# Teensy_Logger_Board.net
KiCad netlist of a schematic drawn in EAGLE
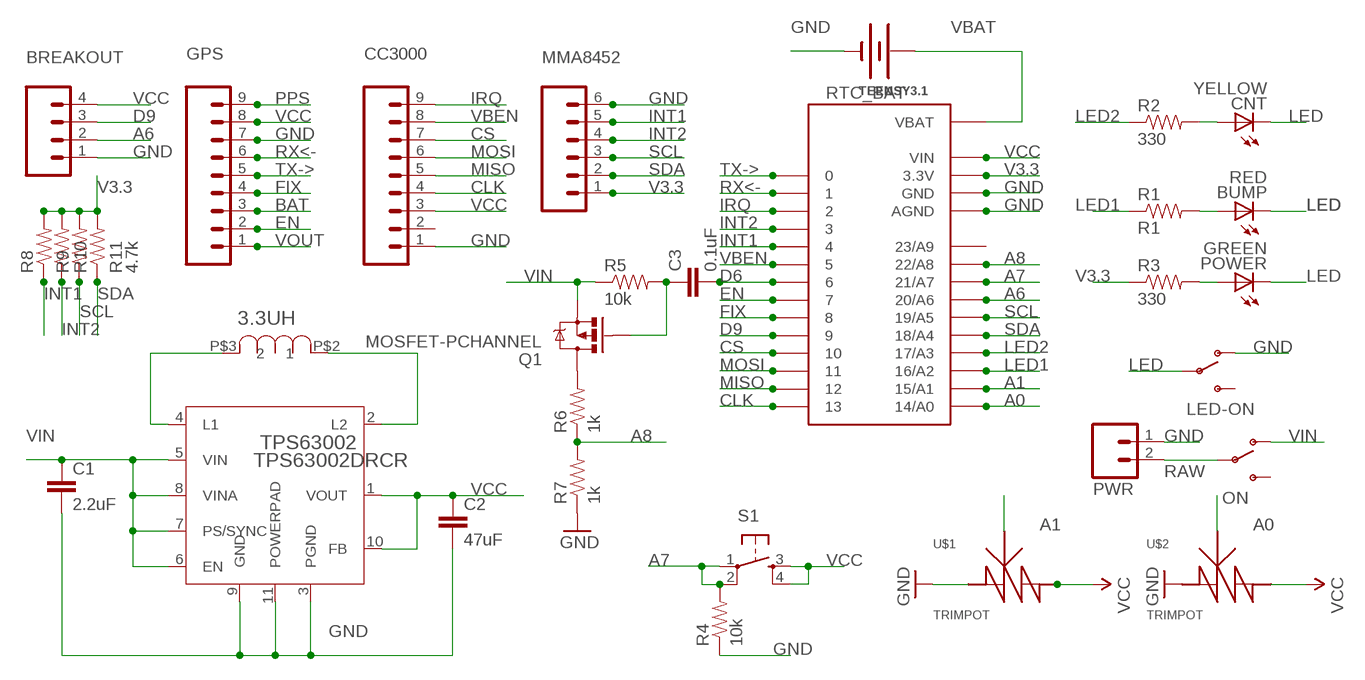
[diagram p0: schematic, sheet 1]

(export (version "E")
  (design (tool "Eeschema 10.0.6"))
  (components
    (comp (ref "3.3UH")
      (value "SRR4028")
      (footprint "eagle-import:POWERINDUCTOR")
      (libsource (lib "eagle-import") (part "SRR4028"))
    )
    (comp (ref "BREAKOUT")
      (value "M04PTH")
      (footprint "eagle-import:1X04")
      (libsource (lib "eagle-import") (part "M04PTH"))
    )
    (comp (ref "BUMP")
      (value "RED")
      (footprint "eagle-import:CHIP-LED0805")
      (libsource (lib "eagle-import") (part "LEDCHIP-LED0805"))
    )
    (comp (ref "C1")
      (value "2.2uF")
      (footprint "eagle-import:1210")
      (libsource (lib "eagle-import") (part "22UF-16V-20%-(1210)"))
    )
    (comp (ref "C2")
      (value "47uF")
      (footprint "eagle-import:0805")
      (libsource (lib "eagle-import") (part "1.0UF-25V-+80/-20(0805)"))
    )
    (comp (ref "C3")
      (value "0.1uF")
      (footprint "eagle-import:0805")
      (libsource (lib "eagle-import") (part "1.0UF-25V-+80/-20(0805)"))
    )
    (comp (ref "CC3000")
      (value "M09")
      (footprint "eagle-import:1X09")
      (libsource (lib "eagle-import") (part "M09"))
    )
    (comp (ref "CNT")
      (value "YELLOW")
      (footprint "eagle-import:CHIP-LED0805")
      (libsource (lib "eagle-import") (part "LEDCHIP-LED0805"))
    )
    (comp (ref "GPS")
      (value "M09")
      (footprint "eagle-import:1X09")
      (libsource (lib "eagle-import") (part "M09"))
    )
    (comp (ref "LED-ON")
      (value "SWITCH-SPDTPTH")
      (footprint "eagle-import:SWITCH-SPDT")
      (libsource (lib "eagle-import") (part "SWITCH-SPDTPTH"))
    )
    (comp (ref "MMA8452")
      (value "M06LOCK")
      (footprint "eagle-import:1X06_LOCK")
      (libsource (lib "eagle-import") (part "M06LOCK"))
    )
    (comp (ref "ON")
      (value "SWITCH-SPDTPTH")
      (footprint "eagle-import:SWITCH-SPDT")
      (libsource (lib "eagle-import") (part "SWITCH-SPDTPTH"))
    )
    (comp (ref "POWER")
      (value "GREEN")
      (footprint "eagle-import:CHIP-LED0805")
      (libsource (lib "eagle-import") (part "LEDCHIP-LED0805"))
    )
    (comp (ref "PWR")
      (value "M02JST-PTH-2")
      (footprint "eagle-import:JST-2-PTH")
      (libsource (lib "eagle-import") (part "M02JST-PTH-2"))
    )
    (comp (ref "Q1")
      (value "MOSFET-PCHANNEL")
      (footprint "eagle-import:SOT23-3")
      (libsource (lib "eagle-import") (part "MOSFET-PCHANNEL"))
    )
    (comp (ref "R1")
      (value "R1")
      (footprint "eagle-import:0805")
      (libsource (lib "eagle-import") (part "RESISTOR0805-RES"))
    )
    (comp (ref "R2")
      (value "330")
      (footprint "eagle-import:0805")
      (libsource (lib "eagle-import") (part "RESISTOR0805-RES"))
    )
    (comp (ref "R3")
      (value "330")
      (footprint "eagle-import:0805")
      (libsource (lib "eagle-import") (part "RESISTOR0805-RES"))
    )
    (comp (ref "R4")
      (value "10k")
      (footprint "eagle-import:0805")
      (libsource (lib "eagle-import") (part "RESISTOR0805-RES"))
    )
    (comp (ref "R5")
      (value "10k")
      (footprint "eagle-import:0805")
      (libsource (lib "eagle-import") (part "RESISTOR0805-RES"))
    )
    (comp (ref "R6")
      (value "1k")
      (footprint "eagle-import:0805")
      (libsource (lib "eagle-import") (part "RESISTOR0805-RES"))
    )
    (comp (ref "R7")
      (value "1k")
      (footprint "eagle-import:0805")
      (libsource (lib "eagle-import") (part "RESISTOR0805-RES"))
    )
    (comp (ref "R8")
      (value "4.7k")
      (footprint "eagle-import:0805")
      (libsource (lib "eagle-import") (part "RESISTOR0805-RES"))
    )
    (comp (ref "R9")
      (value "4.7k")
      (footprint "eagle-import:0805")
      (libsource (lib "eagle-import") (part "RESISTOR0805-RES"))
    )
    (comp (ref "R10")
      (value "4.7k")
      (footprint "eagle-import:0805")
      (libsource (lib "eagle-import") (part "RESISTOR0805-RES"))
    )
    (comp (ref "R11")
      (value "4.7k")
      (footprint "eagle-import:0805")
      (libsource (lib "eagle-import") (part "RESISTOR0805-RES"))
    )
    (comp (ref "RTC_BAT")
      (value "BATTERY12PTH")
      (footprint "eagle-import:BATTCON_12MM_PTH")
      (libsource (lib "eagle-import") (part "BATTERY12PTH"))
    )
    (comp (ref "S1")
      (value "TAC_SWITCHPTH")
      (footprint "eagle-import:TACTILE-PTH")
      (libsource (lib "eagle-import") (part "TAC_SWITCHPTH"))
    )
    (comp (ref "TEENSY3.1")
      (value "TEENSY_3.1_WIFI")
      (footprint "eagle-import:TEENSY_3.1_WIFI")
      (libsource (lib "eagle-import") (part "TEENSY_3.1_WIFI"))
    )
    (comp (ref "TPS63002")
      (value "TPS63002DRCR")
      (footprint "eagle-import:NEW-S-PVSON-N10")
      (libsource (lib "eagle-import") (part "TPS63002DRCR"))
    )
    (comp (ref "U$1")
      (value "TRIMPOT")
      (footprint "eagle-import:TRIMPOT")
      (libsource (lib "eagle-import") (part "TRIMPOT"))
    )
    (comp (ref "U$2")
      (value "TRIMPOT")
      (footprint "eagle-import:TRIMPOT")
      (libsource (lib "eagle-import") (part "TRIMPOT"))
    )
  )
  (nets
    (net (code "1") (name "/A0") (class "Default")
      (node (ref "TEENSY3.1") (pin "14/A0") (pinfunction "14/A0_14/A0") (pintype "bidirectional"))
      (node (ref "U$2") (pin "P$1") (pinfunction "VAR_P$1") (pintype "bidirectional"))
    )
    (net (code "2") (name "/A1") (class "Default")
      (node (ref "TEENSY3.1") (pin "15/A1") (pinfunction "15/A1_15/A1") (pintype "bidirectional"))
      (node (ref "U$1") (pin "P$1") (pinfunction "VAR_P$1") (pintype "bidirectional"))
    )
    (net (code "3") (name "/A6") (class "Default")
      (node (ref "BREAKOUT") (pin "2") (pinfunction "2_2") (pintype "passive"))
      (node (ref "TEENSY3.1") (pin "20/A6") (pinfunction "20/A6_20/A6") (pintype "bidirectional"))
    )
    (net (code "4") (name "/A7") (class "Default")
      (node (ref "R4") (pin "2") (pinfunction "2_2") (pintype "passive"))
      (node (ref "S1") (pin "1") (pinfunction "1_1") (pintype "passive"))
      (node (ref "S1") (pin "2") (pinfunction "2_2") (pintype "passive"))
      (node (ref "TEENSY3.1") (pin "21/A7") (pinfunction "21/A7_21/A7") (pintype "bidirectional"))
    )
    (net (code "5") (name "/A8") (class "Default")
      (node (ref "R6") (pin "1") (pinfunction "1_1") (pintype "passive"))
      (node (ref "R7") (pin "2") (pinfunction "2_2") (pintype "passive"))
      (node (ref "TEENSY3.1") (pin "22/A8") (pinfunction "22/A8_22/A8") (pintype "bidirectional"))
    )
    (net (code "6") (name "/BAT") (class "Default")
      (node (ref "GPS") (pin "3") (pinfunction "3_3") (pintype "passive"))
    )
    (net (code "7") (name "/CLK") (class "Default")
      (node (ref "CC3000") (pin "4") (pinfunction "4_4") (pintype "passive"))
      (node (ref "TEENSY3.1") (pin "13") (pinfunction "13_13") (pintype "bidirectional"))
    )
    (net (code "8") (name "/CS") (class "Default")
      (node (ref "CC3000") (pin "7") (pinfunction "7_7") (pintype "passive"))
      (node (ref "TEENSY3.1") (pin "10") (pinfunction "10_10") (pintype "bidirectional"))
    )
    (net (code "9") (name "/D6") (class "Default")
      (node (ref "C3") (pin "2") (pinfunction "2_2") (pintype "passive"))
      (node (ref "TEENSY3.1") (pin "6") (pinfunction "6_6") (pintype "bidirectional"))
    )
    (net (code "10") (name "/D9") (class "Default")
      (node (ref "BREAKOUT") (pin "3") (pinfunction "3_3") (pintype "passive"))
      (node (ref "TEENSY3.1") (pin "9") (pinfunction "9_9") (pintype "bidirectional"))
    )
    (net (code "11") (name "/EN") (class "Default")
      (node (ref "GPS") (pin "2") (pinfunction "2_2") (pintype "passive"))
      (node (ref "TEENSY3.1") (pin "7") (pinfunction "7_7") (pintype "bidirectional"))
    )
    (net (code "12") (name "/FIX") (class "Default")
      (node (ref "GPS") (pin "4") (pinfunction "4_4") (pintype "passive"))
      (node (ref "TEENSY3.1") (pin "8") (pinfunction "8_8") (pintype "bidirectional"))
    )
    (net (code "13") (name "/INT1") (class "Default")
      (node (ref "MMA8452") (pin "5") (pinfunction "5_5") (pintype "passive"))
      (node (ref "R8") (pin "1") (pinfunction "1_1") (pintype "passive"))
      (node (ref "TEENSY3.1") (pin "4") (pinfunction "4_4") (pintype "bidirectional"))
    )
    (net (code "14") (name "/INT2") (class "Default")
      (node (ref "MMA8452") (pin "4") (pinfunction "4_4") (pintype "passive"))
      (node (ref "R9") (pin "1") (pinfunction "1_1") (pintype "passive"))
      (node (ref "TEENSY3.1") (pin "3") (pinfunction "3_3") (pintype "bidirectional"))
    )
    (net (code "15") (name "/IRQ") (class "Default")
      (node (ref "CC3000") (pin "9") (pinfunction "9_9") (pintype "passive"))
      (node (ref "TEENSY3.1") (pin "2") (pinfunction "2_2") (pintype "bidirectional"))
    )
    (net (code "16") (name "/LED") (class "Default")
      (node (ref "BUMP") (pin "C") (pinfunction "C_C") (pintype "passive"))
      (node (ref "CNT") (pin "C") (pinfunction "C_C") (pintype "passive"))
      (node (ref "LED-ON") (pin "2") (pinfunction "P_2") (pintype "passive"))
      (node (ref "POWER") (pin "C") (pinfunction "C_C") (pintype "passive"))
    )
    (net (code "17") (name "/LED1") (class "Default")
      (node (ref "R1") (pin "1") (pinfunction "1_1") (pintype "passive"))
      (node (ref "TEENSY3.1") (pin "16/A2") (pinfunction "16/A2_16/A2") (pintype "bidirectional"))
    )
    (net (code "18") (name "/LED2") (class "Default")
      (node (ref "R2") (pin "1") (pinfunction "1_1") (pintype "passive"))
      (node (ref "TEENSY3.1") (pin "17/A3") (pinfunction "17/A3_17/A3") (pintype "bidirectional"))
    )
    (net (code "19") (name "/MISO") (class "Default")
      (node (ref "CC3000") (pin "5") (pinfunction "5_5") (pintype "passive"))
      (node (ref "TEENSY3.1") (pin "12") (pinfunction "12_12") (pintype "bidirectional"))
    )
    (net (code "20") (name "/MOSI") (class "Default")
      (node (ref "CC3000") (pin "6") (pinfunction "6_6") (pintype "passive"))
      (node (ref "TEENSY3.1") (pin "11") (pinfunction "11_11") (pintype "bidirectional"))
    )
    (net (code "21") (name "/PPS") (class "Default")
      (node (ref "GPS") (pin "9") (pinfunction "9_9") (pintype "passive"))
    )
    (net (code "22") (name "/RAW") (class "Default")
      (node (ref "ON") (pin "2") (pinfunction "P_2") (pintype "passive"))
      (node (ref "PWR") (pin "2") (pinfunction "2_2") (pintype "passive"))
    )
    (net (code "23") (name "/RX<-") (class "Default")
      (node (ref "GPS") (pin "6") (pinfunction "6_6") (pintype "passive"))
      (node (ref "TEENSY3.1") (pin "1") (pinfunction "1_1") (pintype "bidirectional"))
    )
    (net (code "24") (name "/SCL") (class "Default")
      (node (ref "MMA8452") (pin "3") (pinfunction "3_3") (pintype "passive"))
      (node (ref "R10") (pin "1") (pinfunction "1_1") (pintype "passive"))
      (node (ref "TEENSY3.1") (pin "19/A5") (pinfunction "19/A5_19/A5") (pintype "bidirectional"))
    )
    (net (code "25") (name "/SDA") (class "Default")
      (node (ref "MMA8452") (pin "2") (pinfunction "2_2") (pintype "passive"))
      (node (ref "R11") (pin "1") (pinfunction "1_1") (pintype "passive"))
      (node (ref "TEENSY3.1") (pin "18/A4") (pinfunction "18/A4_18/A4") (pintype "bidirectional"))
    )
    (net (code "26") (name "/TX->") (class "Default")
      (node (ref "GPS") (pin "5") (pinfunction "5_5") (pintype "passive"))
      (node (ref "TEENSY3.1") (pin "0") (pinfunction "0_0") (pintype "bidirectional"))
    )
    (net (code "27") (name "/V3.3") (class "Default")
      (node (ref "MMA8452") (pin "1") (pinfunction "1_1") (pintype "passive"))
      (node (ref "R10") (pin "2") (pinfunction "2_2") (pintype "passive"))
      (node (ref "R11") (pin "2") (pinfunction "2_2") (pintype "passive"))
      (node (ref "R3") (pin "1") (pinfunction "1_1") (pintype "passive"))
      (node (ref "R8") (pin "2") (pinfunction "2_2") (pintype "passive"))
      (node (ref "R9") (pin "2") (pinfunction "2_2") (pintype "passive"))
      (node (ref "TEENSY3.1") (pin "3.3V") (pinfunction "3.3V_3.3V") (pintype "power_in"))
    )
    (net (code "28") (name "/VBAT") (class "Default")
      (node (ref "RTC_BAT") (pin "VCC@1") (pinfunction "+_VCC@1") (pintype "power_in"))
      (node (ref "TEENSY3.1") (pin "VBAT") (pinfunction "VBAT_VBAT") (pintype "power_in"))
    )
    (net (code "29") (name "/VBEN") (class "Default")
      (node (ref "CC3000") (pin "8") (pinfunction "8_8") (pintype "passive"))
      (node (ref "TEENSY3.1") (pin "5") (pinfunction "5_5") (pintype "bidirectional"))
    )
    (net (code "30") (name "/VIN") (class "Default")
      (node (ref "C1") (pin "1") (pinfunction "1_1") (pintype "passive"))
      (node (ref "ON") (pin "1") (pinfunction "O_1") (pintype "passive"))
      (node (ref "Q1") (pin "2") (pinfunction "S_2") (pintype "passive"))
      (node (ref "R5") (pin "1") (pinfunction "1_1") (pintype "passive"))
      (node (ref "TPS63002") (pin "5") (pinfunction "VIN_5") (pintype "passive"))
      (node (ref "TPS63002") (pin "6") (pinfunction "EN_6") (pintype "passive"))
      (node (ref "TPS63002") (pin "7") (pinfunction "PS/SYNC_7") (pintype "passive"))
      (node (ref "TPS63002") (pin "8") (pinfunction "VINA_8") (pintype "passive"))
    )
    (net (code "31") (name "/VOUT") (class "Default")
      (node (ref "GPS") (pin "1") (pinfunction "1_1") (pintype "passive"))
    )
    (net (code "32") (name "GND") (class "Default")
      (node (ref "BREAKOUT") (pin "1") (pinfunction "1_1") (pintype "passive"))
      (node (ref "C1") (pin "2") (pinfunction "2_2") (pintype "passive"))
      (node (ref "C2") (pin "2") (pinfunction "2_2") (pintype "passive"))
      (node (ref "CC3000") (pin "1") (pinfunction "1_1") (pintype "passive"))
      (node (ref "GPS") (pin "7") (pinfunction "7_7") (pintype "passive"))
      (node (ref "LED-ON") (pin "1") (pinfunction "O_1") (pintype "passive"))
      (node (ref "MMA8452") (pin "6") (pinfunction "6_6") (pintype "passive"))
      (node (ref "PWR") (pin "1") (pinfunction "1_1") (pintype "passive"))
      (node (ref "R4") (pin "1") (pinfunction "1_1") (pintype "passive"))
      (node (ref "R7") (pin "1") (pinfunction "1_1") (pintype "passive"))
      (node (ref "RTC_BAT") (pin "GND") (pinfunction "-_GND") (pintype "power_in"))
      (node (ref "TEENSY3.1") (pin "AGND") (pinfunction "AGND_AGND") (pintype "power_in"))
      (node (ref "TEENSY3.1") (pin "GND") (pinfunction "GND_GND") (pintype "power_in"))
      (node (ref "TPS63002") (pin "11") (pinfunction "POWERPAD_11") (pintype "passive"))
      (node (ref "TPS63002") (pin "3") (pinfunction "PGND_3") (pintype "passive"))
      (node (ref "TPS63002") (pin "9") (pinfunction "GND_9") (pintype "passive"))
      (node (ref "U$1") (pin "P$2") (pinfunction "IN_P$2") (pintype "bidirectional"))
      (node (ref "U$2") (pin "P$2") (pinfunction "IN_P$2") (pintype "bidirectional"))
    )
    (net (code "33") (name "Net-(3.3UH-1)") (class "Default")
      (node (ref "3.3UH") (pin "P$2") (pinfunction "1_P$2") (pintype "passive"))
      (node (ref "TPS63002") (pin "2") (pinfunction "L2_2") (pintype "passive"))
    )
    (net (code "34") (name "Net-(3.3UH-2)") (class "Default")
      (node (ref "3.3UH") (pin "P$3") (pinfunction "2_P$3") (pintype "passive"))
      (node (ref "TPS63002") (pin "4") (pinfunction "L1_4") (pintype "passive"))
    )
    (net (code "35") (name "Net-(BUMP-PadA)") (class "Default")
      (node (ref "BUMP") (pin "A") (pinfunction "A_A") (pintype "passive"))
      (node (ref "R1") (pin "2") (pinfunction "2_2") (pintype "passive"))
    )
    (net (code "36") (name "Net-(CNT-PadA)") (class "Default")
      (node (ref "CNT") (pin "A") (pinfunction "A_A") (pintype "passive"))
      (node (ref "R2") (pin "2") (pinfunction "2_2") (pintype "passive"))
    )
    (net (code "37") (name "Net-(POWER-PadA)") (class "Default")
      (node (ref "POWER") (pin "A") (pinfunction "A_A") (pintype "passive"))
      (node (ref "R3") (pin "2") (pinfunction "2_2") (pintype "passive"))
    )
    (net (code "38") (name "Net-(Q1-D)") (class "Default")
      (node (ref "Q1") (pin "3") (pinfunction "D_3") (pintype "passive"))
      (node (ref "R6") (pin "2") (pinfunction "2_2") (pintype "passive"))
    )
    (net (code "39") (name "Net-(Q1-G)") (class "Default")
      (node (ref "C3") (pin "1") (pinfunction "1_1") (pintype "passive"))
      (node (ref "Q1") (pin "1") (pinfunction "G_1") (pintype "passive"))
      (node (ref "R5") (pin "2") (pinfunction "2_2") (pintype "passive"))
    )
    (net (code "40") (name "VCC") (class "Default")
      (node (ref "BREAKOUT") (pin "4") (pinfunction "4_4") (pintype "passive"))
      (node (ref "C2") (pin "1") (pinfunction "1_1") (pintype "passive"))
      (node (ref "CC3000") (pin "3") (pinfunction "3_3") (pintype "passive"))
      (node (ref "GPS") (pin "8") (pinfunction "8_8") (pintype "passive"))
      (node (ref "S1") (pin "3") (pinfunction "3_3") (pintype "passive"))
      (node (ref "S1") (pin "4") (pinfunction "4_4") (pintype "passive"))
      (node (ref "TEENSY3.1") (pin "VIN") (pinfunction "VIN_VIN") (pintype "power_in"))
      (node (ref "TPS63002") (pin "1") (pinfunction "VOUT_1") (pintype "passive"))
      (node (ref "TPS63002") (pin "10") (pinfunction "FB_10") (pintype "passive"))
      (node (ref "U$1") (pin "P$3") (pinfunction "OUT_P$3") (pintype "bidirectional"))
      (node (ref "U$2") (pin "P$3") (pinfunction "OUT_P$3") (pintype "bidirectional"))
    )
    (net (code "41") (name "unconnected-(CC3000-Pad2)") (class "Default")
      (node (ref "CC3000") (pin "2") (pinfunction "2_2") (pintype "passive"))
    )
    (net (code "42") (name "unconnected-(LED-ON-S-Pad3)") (class "Default")
      (node (ref "LED-ON") (pin "3") (pinfunction "S_3") (pintype "passive"))
    )
    (net (code "43") (name "unconnected-(ON-S-Pad3)") (class "Default")
      (node (ref "ON") (pin "3") (pinfunction "S_3") (pintype "passive"))
    )
    (net (code "44") (name "unconnected-(TEENSY3.1-Pad23{slash}A9)") (class "Default")
      (node (ref "TEENSY3.1") (pin "23/A9") (pinfunction "23/A9_23/A9") (pintype "bidirectional"))
    )
  )
)
